# Keypad_Temp_BatLevel.net
KiCad netlist of a schematic drawn in Altium Designer
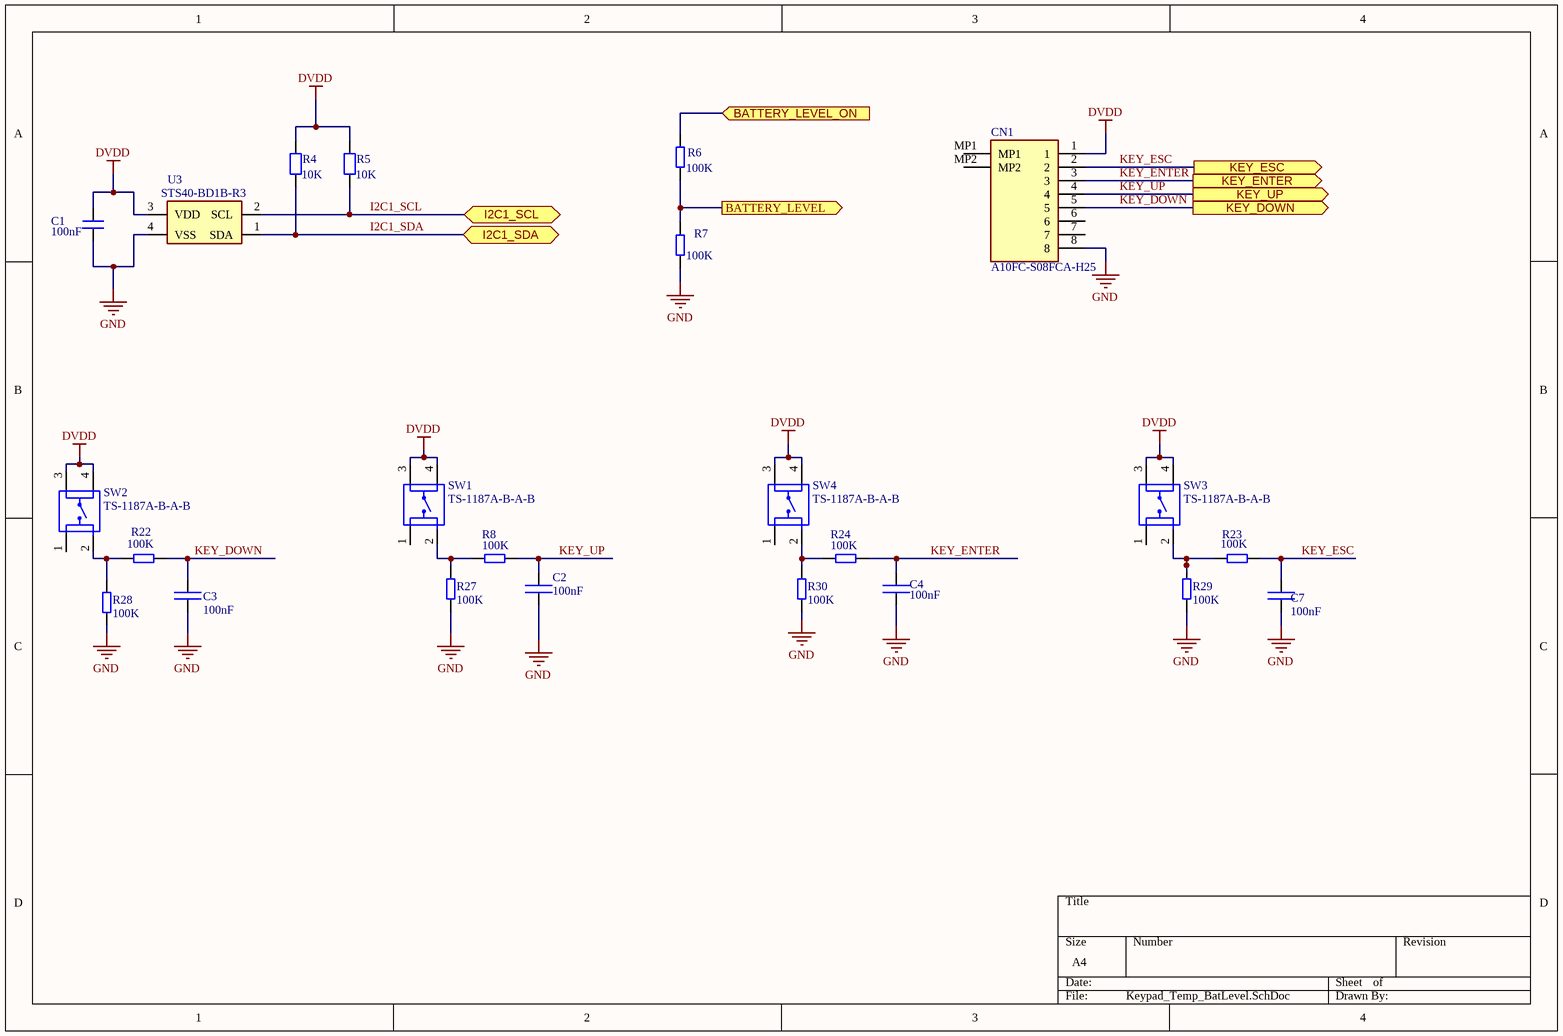
[diagram p0: Keypad_Temp_BatLevel.SchDoc]

(export (version "E")
  (design (tool "Eeschema 10.0.6"))
  (components
    (comp (ref "C1")
      (value "100nF")
      (footprint "CAP_SM0603_YAGEOCC2_N")
      (description "CAP 100nF SM0603 X7R 50V YAGEO CC2")
      (fields
        (field (name "MANUFACTURER") "Yageo")
        (field (name "MANUFACTURER PART NUMBER") "CC0603KRX7R9BB104")
      )
      (libsource (lib "") (part "CC0603KRX7R9BB104_1"))
    )
    (comp (ref "C2")
      (value "100nF")
      (footprint "CAP_SM0603_YAGEOCC2_N")
      (description "CAP 100nF SM0603 X7R 50V YAGEO CC2")
      (fields
        (field (name "MANUFACTURER") "Yageo")
        (field (name "MANUFACTURER PART NUMBER") "CC0603KRX7R9BB104")
      )
      (libsource (lib "yageo") (part "CC0603KRX7R9BB104"))
    )
    (comp (ref "C3")
      (value "100nF")
      (footprint "CAP_SM0603_YAGEOCC2_N")
      (description "CAP 100nF SM0603 X7R 50V YAGEO CC2")
      (fields
        (field (name "MANUFACTURER") "Yageo")
        (field (name "MANUFACTURER PART NUMBER") "CC0603KRX7R9BB104")
      )
      (libsource (lib "yageo") (part "CC0603KRX7R9BB104"))
    )
    (comp (ref "C4")
      (value "100nF")
      (footprint "CAP_SM0603_YAGEOCC2_N")
      (description "CAP 100nF SM0603 X7R 50V YAGEO CC2")
      (fields
        (field (name "MANUFACTURER") "Yageo")
        (field (name "MANUFACTURER PART NUMBER") "CC0603KRX7R9BB104")
      )
      (libsource (lib "yageo") (part "CC0603KRX7R9BB104"))
    )
    (comp (ref "C7")
      (value "100nF")
      (footprint "CAP_SM0603_YAGEOCC2_N")
      (description "CAP 100nF SM0603 X7R 50V YAGEO CC2")
      (fields
        (field (name "MANUFACTURER") "Yageo")
        (field (name "MANUFACTURER PART NUMBER") "CC0603KRX7R9BB104")
      )
      (libsource (lib "yageo") (part "CC0603KRX7R9BB104"))
    )
    (comp (ref "CN1")
      (value "A10FC-S08FCA-H25")
      (footprint "849528")
      (description "FFC/FPC Connector 8 Position 1mm Pitch Bottom Contact Surface Mount, Right Angle -40℃~+85℃")
      (fields (field (name "MANUFACTURER") "JXTCONN") (field (name "VENDOR PART NUMBER") "C42447839"))
      (libsource (lib "flowmeet") (part "A10FC-S08FCA-H25"))
    )
    (comp (ref "R4")
      (value "10K")
      (footprint "RES_SM0603_YAGEORC_N")
      (description "RES 10K SM0603 YAGEO RC_L")
      (fields
        (field (name "MANUFACTURER") "Yageo")
        (field (name "MANUFACTURER PART NUMBER") "RC0603FR-0710KL")
      )
      (libsource (lib "yageo") (part "RC0603FR-0710KL"))
    )
    (comp (ref "R5")
      (value "10K")
      (footprint "RES_SM0603_YAGEORC_N")
      (description "RES 10K SM0603 YAGEO RC_L")
      (fields
        (field (name "MANUFACTURER") "Yageo")
        (field (name "MANUFACTURER PART NUMBER") "RC0603FR-0710KL")
      )
      (libsource (lib "yageo") (part "RC0603FR-0710KL"))
    )
    (comp (ref "R6")
      (value "100K")
      (footprint "RES_SM0603_YAGEORC_N")
      (description "RES 100K SM0603 YAGEO RC_L")
      (fields
        (field (name "MANUFACTURER") "Yageo")
        (field (name "MANUFACTURER PART NUMBER") "RC0603FR-13100KL")
      )
      (libsource (lib "") (part "RC0603FR-13100KL_1"))
    )
    (comp (ref "R7")
      (value "100K")
      (footprint "RES_SM0603_YAGEORC_N")
      (description "RES 100K SM0603 YAGEO RC_L")
      (fields
        (field (name "MANUFACTURER") "Yageo")
        (field (name "MANUFACTURER PART NUMBER") "RC0603FR-13100KL")
      )
      (libsource (lib "") (part "RC0603FR-13100KL_1"))
    )
    (comp (ref "R8")
      (value "100K")
      (footprint "RES_SM0603_YAGEORC_N")
      (description "RES 100K SM0603 YAGEO RC_L")
      (fields
        (field (name "MANUFACTURER") "Yageo")
        (field (name "MANUFACTURER PART NUMBER") "RC0603FR-13100KL")
      )
      (libsource (lib "yageo") (part "RC0603FR-13100KL"))
    )
    (comp (ref "R22")
      (value "100K")
      (footprint "RES_SM0603_YAGEORC_N")
      (description "RES 100K SM0603 YAGEO RC_L")
      (fields
        (field (name "MANUFACTURER") "Yageo")
        (field (name "MANUFACTURER PART NUMBER") "RC0603FR-13100KL")
      )
      (libsource (lib "yageo") (part "RC0603FR-13100KL"))
    )
    (comp (ref "R23")
      (value "100K")
      (footprint "RES_SM0603_YAGEORC_N")
      (description "RES 100K SM0603 YAGEO RC_L")
      (fields
        (field (name "MANUFACTURER") "Yageo")
        (field (name "MANUFACTURER PART NUMBER") "RC0603FR-13100KL")
      )
      (libsource (lib "yageo") (part "RC0603FR-13100KL"))
    )
    (comp (ref "R24")
      (value "100K")
      (footprint "RES_SM0603_YAGEORC_N")
      (description "RES 100K SM0603 YAGEO RC_L")
      (fields
        (field (name "MANUFACTURER") "Yageo")
        (field (name "MANUFACTURER PART NUMBER") "RC0603FR-13100KL")
      )
      (libsource (lib "yageo") (part "RC0603FR-13100KL"))
    )
    (comp (ref "R27")
      (value "100K")
      (footprint "RES_SM0603_YAGEORC_N")
      (description "RES 100K SM0603 YAGEO RC_L")
      (fields
        (field (name "MANUFACTURER") "Yageo")
        (field (name "MANUFACTURER PART NUMBER") "RC0603FR-13100KL")
      )
      (libsource (lib "") (part "RC0603FR-13100KL_1"))
    )
    (comp (ref "R28")
      (value "100K")
      (footprint "RES_SM0603_YAGEORC_N")
      (description "RES 100K SM0603 YAGEO RC_L")
      (fields
        (field (name "MANUFACTURER") "Yageo")
        (field (name "MANUFACTURER PART NUMBER") "RC0603FR-13100KL")
      )
      (libsource (lib "") (part "RC0603FR-13100KL_1"))
    )
    (comp (ref "R29")
      (value "100K")
      (footprint "RES_SM0603_YAGEORC_N")
      (description "RES 100K SM0603 YAGEO RC_L")
      (fields
        (field (name "MANUFACTURER") "Yageo")
        (field (name "MANUFACTURER PART NUMBER") "RC0603FR-13100KL")
      )
      (libsource (lib "") (part "RC0603FR-13100KL_1"))
    )
    (comp (ref "R30")
      (value "100K")
      (footprint "RES_SM0603_YAGEORC_N")
      (description "RES 100K SM0603 YAGEO RC_L")
      (fields
        (field (name "MANUFACTURER") "Yageo")
        (field (name "MANUFACTURER PART NUMBER") "RC0603FR-13100KL")
      )
      (libsource (lib "") (part "RC0603FR-13100KL_1"))
    )
    (comp (ref "SW1")
      (value "TS-1187A-B-A-B")
      (footprint "TS-1187A-B-A-B")
      (description "Switch tactile SMD")
      (fields (field (name "MANUFACTURER") "XKB Connectivity") (field (name "VENDOR PART NUMBER") "C318884"))
      (libsource (lib "flowmeet") (part "TS-1187A-B-A-B"))
    )
    (comp (ref "SW2")
      (value "TS-1187A-B-A-B")
      (footprint "TS-1187A-B-A-B")
      (description "Switch tactile SMD")
      (fields (field (name "MANUFACTURER") "XKB Connectivity") (field (name "VENDOR PART NUMBER") "C318884"))
      (libsource (lib "flowmeet") (part "TS-1187A-B-A-B"))
    )
    (comp (ref "SW3")
      (value "TS-1187A-B-A-B")
      (footprint "TS-1187A-B-A-B")
      (description "Switch tactile SMD")
      (fields (field (name "MANUFACTURER") "XKB Connectivity") (field (name "VENDOR PART NUMBER") "C318884"))
      (libsource (lib "flowmeet") (part "TS-1187A-B-A-B"))
    )
    (comp (ref "SW4")
      (value "TS-1187A-B-A-B")
      (footprint "TS-1187A-B-A-B")
      (description "Switch tactile SMD")
      (fields (field (name "MANUFACTURER") "XKB Connectivity") (field (name "VENDOR PART NUMBER") "C318884"))
      (libsource (lib "flowmeet") (part "TS-1187A-B-A-B"))
    )
    (comp (ref "U3")
      (value "STS40-BD1B-R3")
      (footprint "STS40BD1BR3")
      (description "Board Mount Temperature Sensors Base Accuracy Version, I2C Address 0x45")
      (fields (field (name "MANUFACTURER") "Sensirion"))
      (libsource (lib "flowmeet") (part "STS40-BD1B-R3"))
    )
  )
  (nets
    (net (code "1") (name "/BATTERY_LEVEL") (class "Default")
      (node (ref "R6") (pin "1") (pintype "passive"))
      (node (ref "R7") (pin "2") (pintype "passive"))
    )
    (net (code "2") (name "/BATTERY_LEVEL_ON") (class "Default")
      (node (ref "R6") (pin "2") (pintype "passive"))
    )
    (net (code "3") (name "/I2C1_SCL") (class "Default")
      (node (ref "R5") (pin "1") (pintype "passive"))
      (node (ref "U3") (pin "2") (pinfunction "SCL_2") (pintype "passive"))
    )
    (net (code "4") (name "/I2C1_SDA") (class "Default")
      (node (ref "R4") (pin "1") (pintype "passive"))
      (node (ref "U3") (pin "1") (pinfunction "SDA_1") (pintype "passive"))
    )
    (net (code "5") (name "/KEY_DOWN") (class "Default")
      (node (ref "C3") (pin "2") (pintype "passive"))
      (node (ref "CN1") (pin "5") (pinfunction "5_5") (pintype "passive"))
      (node (ref "R22") (pin "2") (pintype "passive"))
    )
    (net (code "6") (name "/KEY_ENTER") (class "Default")
      (node (ref "C4") (pin "1") (pintype "passive"))
      (node (ref "CN1") (pin "3") (pinfunction "3_3") (pintype "passive"))
      (node (ref "R24") (pin "2") (pintype "passive"))
    )
    (net (code "7") (name "/KEY_ESC") (class "Default")
      (node (ref "C7") (pin "1") (pintype "passive"))
      (node (ref "CN1") (pin "2") (pinfunction "2_2") (pintype "passive"))
      (node (ref "R23") (pin "2") (pintype "passive"))
    )
    (net (code "8") (name "/KEY_UP") (class "Default")
      (node (ref "C2") (pin "1") (pintype "passive"))
      (node (ref "CN1") (pin "4") (pinfunction "4_4") (pintype "passive"))
      (node (ref "R8") (pin "2") (pintype "passive"))
    )
    (net (code "9") (name "DVDD") (class "Default")
      (node (ref "C1") (pin "2") (pintype "passive"))
      (node (ref "CN1") (pin "1") (pinfunction "1_1") (pintype "passive"))
      (node (ref "R4") (pin "2") (pintype "passive"))
      (node (ref "R5") (pin "2") (pintype "passive"))
      (node (ref "SW1") (pin "3") (pinfunction "g_3") (pintype "passive"))
      (node (ref "SW1") (pin "4") (pinfunction "4_4") (pintype "passive"))
      (node (ref "SW2") (pin "3") (pinfunction "g_3") (pintype "passive"))
      (node (ref "SW2") (pin "4") (pinfunction "4_4") (pintype "passive"))
      (node (ref "SW3") (pin "3") (pinfunction "g_3") (pintype "passive"))
      (node (ref "SW3") (pin "4") (pinfunction "4_4") (pintype "passive"))
      (node (ref "SW4") (pin "3") (pinfunction "g_3") (pintype "passive"))
      (node (ref "SW4") (pin "4") (pinfunction "4_4") (pintype "passive"))
      (node (ref "U3") (pin "3") (pinfunction "VDD_3") (pintype "passive"))
    )
    (net (code "10") (name "GND") (class "Default")
      (node (ref "C1") (pin "1") (pintype "passive"))
      (node (ref "C2") (pin "2") (pintype "passive"))
      (node (ref "C3") (pin "1") (pintype "passive"))
      (node (ref "C4") (pin "2") (pintype "passive"))
      (node (ref "C7") (pin "2") (pintype "passive"))
      (node (ref "CN1") (pin "8") (pinfunction "8_8") (pintype "passive"))
      (node (ref "R27") (pin "1") (pintype "passive"))
      (node (ref "R28") (pin "1") (pintype "passive"))
      (node (ref "R29") (pin "1") (pintype "passive"))
      (node (ref "R30") (pin "1") (pintype "passive"))
      (node (ref "R7") (pin "1") (pintype "passive"))
      (node (ref "U3") (pin "4") (pinfunction "VSS_4") (pintype "passive"))
    )
    (net (code "11") (name "Net-(R22-Pad1)") (class "Default")
      (node (ref "R22") (pin "1") (pintype "passive"))
      (node (ref "R28") (pin "2") (pintype "passive"))
      (node (ref "SW2") (pin "2") (pinfunction "2_2") (pintype "passive"))
    )
    (net (code "12") (name "Net-(R23-Pad1)") (class "Default")
      (node (ref "R23") (pin "1") (pintype "passive"))
      (node (ref "R29") (pin "2") (pintype "passive"))
      (node (ref "SW3") (pin "2") (pinfunction "2_2") (pintype "passive"))
    )
    (net (code "13") (name "Net-(R24-Pad1)") (class "Default")
      (node (ref "R24") (pin "1") (pintype "passive"))
      (node (ref "R30") (pin "2") (pintype "passive"))
      (node (ref "SW4") (pin "2") (pinfunction "2_2") (pintype "passive"))
    )
    (net (code "14") (name "Net-(R27-Pad2)") (class "Default")
      (node (ref "R27") (pin "2") (pintype "passive"))
      (node (ref "R8") (pin "1") (pintype "passive"))
      (node (ref "SW1") (pin "2") (pinfunction "2_2") (pintype "passive"))
    )
    (net (code "15") (name "unconnected-(CN1-Pad6)") (class "Default")
      (node (ref "CN1") (pin "6") (pinfunction "6_6") (pintype "passive"))
    )
    (net (code "16") (name "unconnected-(CN1-Pad7)") (class "Default")
      (node (ref "CN1") (pin "7") (pinfunction "7_7") (pintype "passive"))
    )
    (net (code "17") (name "unconnected-(CN1-PadMP1)") (class "Default")
      (node (ref "CN1") (pin "MP1") (pinfunction "MP1_MP1") (pintype "passive"))
    )
    (net (code "18") (name "unconnected-(CN1-PadMP2)") (class "Default")
      (node (ref "CN1") (pin "MP2") (pinfunction "MP2_MP2") (pintype "passive"))
    )
    (net (code "19") (name "unconnected-(SW1-Pad1)") (class "Default")
      (node (ref "SW1") (pin "1") (pinfunction "1_1") (pintype "passive"))
    )
    (net (code "20") (name "unconnected-(SW2-Pad1)") (class "Default")
      (node (ref "SW2") (pin "1") (pinfunction "1_1") (pintype "passive"))
    )
    (net (code "21") (name "unconnected-(SW3-Pad1)") (class "Default")
      (node (ref "SW3") (pin "1") (pinfunction "1_1") (pintype "passive"))
    )
    (net (code "22") (name "unconnected-(SW4-Pad1)") (class "Default")
      (node (ref "SW4") (pin "1") (pinfunction "1_1") (pintype "passive"))
    )
  )
)
